# CamBoard.net
KiCad netlist of a schematic drawn in Altium Designer
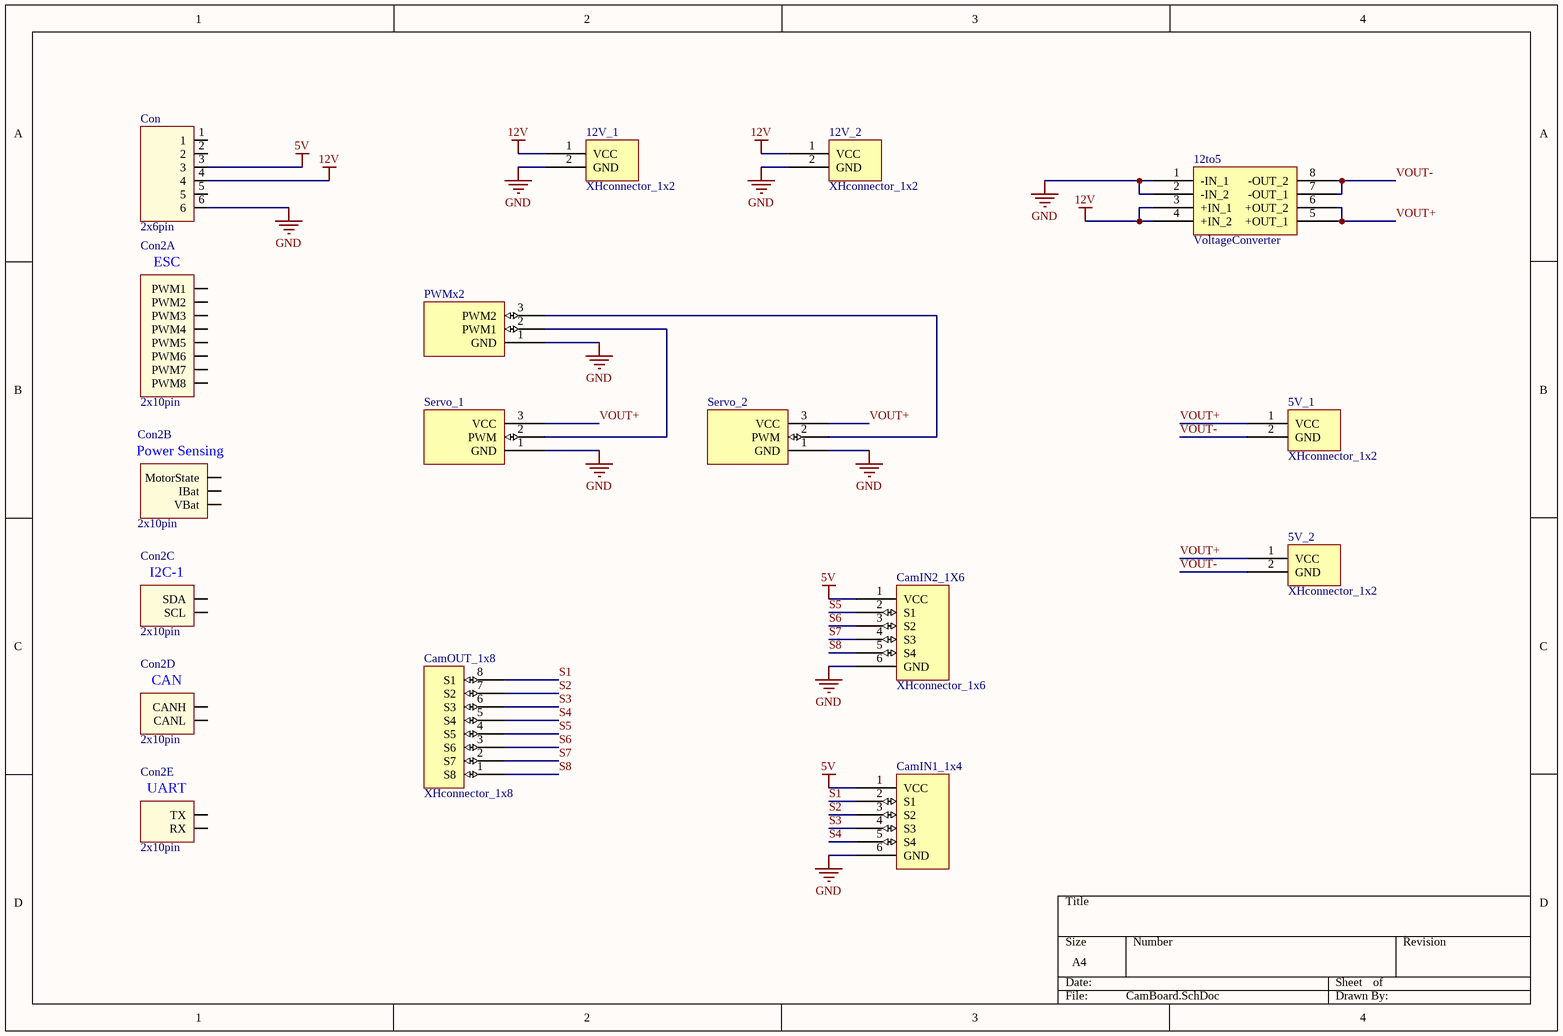
[diagram p0: CamBoard.SchDoc]

(export (version "E")
  (design (tool "Eeschema 10.0.6"))
  (components
    (comp (ref "5V_1")
      (value "XHconnector_1x2")
      (footprint "XH1x2")
      (libsource (lib "Schlib1") (part "XHconnector_1x2"))
    )
    (comp (ref "5V_2")
      (value "XHconnector_1x2")
      (footprint "XH1x2")
      (libsource (lib "Schlib1") (part "XHconnector_1x2"))
    )
    (comp (ref "12to5")
      (value "VoltageConverter")
      (footprint "converter")
      (libsource (lib "Schlib1") (part "VoltageConverter"))
    )
    (comp (ref "12V_1")
      (value "XHconnector_1x2")
      (footprint "XH1x2")
      (libsource (lib "Schlib1") (part "XHconnector_1x2"))
    )
    (comp (ref "12V_2")
      (value "XHconnector_1x2")
      (footprint "XH1x2")
      (libsource (lib "Schlib1") (part "XHconnector_1x2"))
    )
    (comp (ref "CamIN1_1x4")
      (value "XHconnector_1x6")
      (footprint "XH1x6")
      (libsource (lib "Schlib1") (part "XHconnector_1x6"))
    )
    (comp (ref "CamIN2_1X6")
      (value "XHconnector_1x6")
      (footprint "XH1x6")
      (libsource (lib "Schlib1") (part "XHconnector_1x6"))
    )
    (comp (ref "CamOUT_1x8")
      (value "XHconnector_1x8")
      (footprint "XH1x8")
      (libsource (lib "Schlib1") (part "XHconnector_1x8"))
    )
    (comp (ref "Con") (value "2x6pin") (footprint "2x6pin") (libsource (lib "Schlib1") (part "2x6pin")))
    (comp (ref "Con2") (value "2x10pin") (footprint "2x10pin") (libsource (lib "Schlib1") (part "2x10pin")))
    (comp (ref "PWMx2") (value "PWMx2") (footprint "XH1x3") (libsource (lib "Schlib1") (part "PWMx2")))
    (comp (ref "Servo_1") (value "Servo") (footprint "XH1x3") (libsource (lib "Schlib1") (part "Servo")))
    (comp (ref "Servo_2") (value "Servo") (footprint "XH1x3") (libsource (lib "Schlib1") (part "Servo")))
  )
  (nets
    (net (code "1") (name "/S1") (class "Default")
      (node (ref "CamIN1_1x4") (pin "2") (pinfunction "S1_2") (pintype "bidirectional"))
      (node (ref "CamOUT_1x8") (pin "8") (pinfunction "S1_8") (pintype "bidirectional"))
    )
    (net (code "2") (name "/S2") (class "Default")
      (node (ref "CamIN1_1x4") (pin "3") (pinfunction "S2_3") (pintype "bidirectional"))
      (node (ref "CamOUT_1x8") (pin "7") (pinfunction "S2_7") (pintype "bidirectional"))
    )
    (net (code "3") (name "/S3") (class "Default")
      (node (ref "CamIN1_1x4") (pin "4") (pinfunction "S3_4") (pintype "bidirectional"))
      (node (ref "CamOUT_1x8") (pin "6") (pinfunction "S3_6") (pintype "bidirectional"))
    )
    (net (code "4") (name "/S4") (class "Default")
      (node (ref "CamIN1_1x4") (pin "5") (pinfunction "S4_5") (pintype "bidirectional"))
      (node (ref "CamOUT_1x8") (pin "5") (pinfunction "S4_5") (pintype "bidirectional"))
    )
    (net (code "5") (name "/S5") (class "Default")
      (node (ref "CamIN2_1X6") (pin "2") (pinfunction "S1_2") (pintype "bidirectional"))
      (node (ref "CamOUT_1x8") (pin "4") (pinfunction "S5_4") (pintype "bidirectional"))
    )
    (net (code "6") (name "/S6") (class "Default")
      (node (ref "CamIN2_1X6") (pin "3") (pinfunction "S2_3") (pintype "bidirectional"))
      (node (ref "CamOUT_1x8") (pin "3") (pinfunction "S6_3") (pintype "bidirectional"))
    )
    (net (code "7") (name "/S7") (class "Default")
      (node (ref "CamIN2_1X6") (pin "4") (pinfunction "S3_4") (pintype "bidirectional"))
      (node (ref "CamOUT_1x8") (pin "2") (pinfunction "S7_2") (pintype "bidirectional"))
    )
    (net (code "8") (name "/S8") (class "Default")
      (node (ref "CamIN2_1X6") (pin "5") (pinfunction "S4_5") (pintype "bidirectional"))
      (node (ref "CamOUT_1x8") (pin "1") (pinfunction "S8_1") (pintype "bidirectional"))
    )
    (net (code "9") (name "/VOUT+") (class "Default")
      (node (ref "12to5") (pin "5") (pinfunction "+OUT_1_5") (pintype "passive"))
      (node (ref "12to5") (pin "6") (pinfunction "+OUT_2_6") (pintype "passive"))
      (node (ref "5V_1") (pin "1") (pinfunction "VCC_1") (pintype "power_in"))
      (node (ref "5V_2") (pin "1") (pinfunction "VCC_1") (pintype "power_in"))
      (node (ref "Servo_1") (pin "3") (pinfunction "VCC_3") (pintype "power_in"))
      (node (ref "Servo_2") (pin "3") (pinfunction "VCC_3") (pintype "power_in"))
    )
    (net (code "10") (name "/VOUT-") (class "Default")
      (node (ref "12to5") (pin "7") (pinfunction "-OUT_1_7") (pintype "power_in"))
      (node (ref "12to5") (pin "8") (pinfunction "-OUT_2_8") (pintype "power_in"))
      (node (ref "5V_1") (pin "2") (pinfunction "GND_2") (pintype "power_in"))
      (node (ref "5V_2") (pin "2") (pinfunction "GND_2") (pintype "power_in"))
    )
    (net (code "11") (name "5V") (class "Default")
      (node (ref "CamIN1_1x4") (pin "1") (pinfunction "VCC_1") (pintype "power_in"))
      (node (ref "CamIN2_1X6") (pin "1") (pinfunction "VCC_1") (pintype "power_in"))
      (node (ref "Con") (pin "3") (pinfunction "3_3") (pintype "power_in"))
    )
    (net (code "12") (name "12V") (class "Default")
      (node (ref "12V_1") (pin "1") (pinfunction "VCC_1") (pintype "power_in"))
      (node (ref "12V_2") (pin "1") (pinfunction "VCC_1") (pintype "power_in"))
      (node (ref "12to5") (pin "3") (pinfunction "+IN_1_3") (pintype "power_in"))
      (node (ref "12to5") (pin "4") (pinfunction "+IN_2_4") (pintype "power_in"))
      (node (ref "Con") (pin "4") (pinfunction "4_4") (pintype "power_in"))
    )
    (net (code "13") (name "GND") (class "Default")
      (node (ref "12V_1") (pin "2") (pinfunction "GND_2") (pintype "power_in"))
      (node (ref "12V_2") (pin "2") (pinfunction "GND_2") (pintype "power_in"))
      (node (ref "12to5") (pin "1") (pinfunction "-IN_1_1") (pintype "passive"))
      (node (ref "12to5") (pin "2") (pinfunction "-IN_2_2") (pintype "passive"))
      (node (ref "CamIN1_1x4") (pin "6") (pinfunction "GND_6") (pintype "power_in"))
      (node (ref "CamIN2_1X6") (pin "6") (pinfunction "GND_6") (pintype "power_in"))
      (node (ref "Con") (pin "6") (pinfunction "6_6") (pintype "power_in"))
      (node (ref "PWMx2") (pin "1") (pinfunction "GND_1") (pintype "power_in"))
      (node (ref "Servo_1") (pin "1") (pinfunction "GND_1") (pintype "power_in"))
      (node (ref "Servo_2") (pin "1") (pinfunction "GND_1") (pintype "power_in"))
    )
    (net (code "14") (name "Net-(PWMx2-PWM1)") (class "Default")
      (node (ref "PWMx2") (pin "2") (pinfunction "PWM1_2") (pintype "bidirectional"))
      (node (ref "Servo_1") (pin "2") (pinfunction "PWM_2") (pintype "bidirectional"))
    )
    (net (code "15") (name "Net-(PWMx2-PWM2)") (class "Default")
      (node (ref "PWMx2") (pin "3") (pinfunction "PWM2_3") (pintype "bidirectional"))
      (node (ref "Servo_2") (pin "2") (pinfunction "PWM_2") (pintype "bidirectional"))
    )
    (net (code "16") (name "unconnected-(Con-Pad1)") (class "Default")
      (node (ref "Con") (pin "1") (pinfunction "1_1") (pintype "power_in"))
    )
    (net (code "17") (name "unconnected-(Con-Pad2)") (class "Default")
      (node (ref "Con") (pin "2") (pinfunction "2_2") (pintype "power_in"))
    )
    (net (code "18") (name "unconnected-(Con-Pad5)") (class "Default")
      (node (ref "Con") (pin "5") (pinfunction "5_5") (pintype "power_in"))
    )
    (net (code "19") (name "unconnected-(Con2A-PWM1-Pad1)") (class "Default")
      (node (ref "Con2") (pin "1") (pinfunction "PWM1_1") (pintype "passive"))
    )
    (net (code "20") (name "unconnected-(Con2A-PWM2-Pad2)") (class "Default")
      (node (ref "Con2") (pin "2") (pinfunction "PWM2_2") (pintype "passive"))
    )
    (net (code "21") (name "unconnected-(Con2A-PWM3-Pad3)") (class "Default")
      (node (ref "Con2") (pin "3") (pinfunction "PWM3_3") (pintype "passive"))
    )
    (net (code "22") (name "unconnected-(Con2A-PWM4-Pad4)") (class "Default")
      (node (ref "Con2") (pin "4") (pinfunction "PWM4_4") (pintype "passive"))
    )
    (net (code "23") (name "unconnected-(Con2A-PWM5-Pad5)") (class "Default")
      (node (ref "Con2") (pin "5") (pinfunction "PWM5_5") (pintype "passive"))
    )
    (net (code "24") (name "unconnected-(Con2A-PWM6-Pad6)") (class "Default")
      (node (ref "Con2") (pin "6") (pinfunction "PWM6_6") (pintype "passive"))
    )
    (net (code "25") (name "unconnected-(Con2A-PWM7-Pad7)") (class "Default")
      (node (ref "Con2") (pin "7") (pinfunction "PWM7_7") (pintype "passive"))
    )
    (net (code "26") (name "unconnected-(Con2A-PWM8-Pad8)") (class "Default")
      (node (ref "Con2") (pin "8") (pinfunction "PWM8_8") (pintype "passive"))
    )
    (net (code "27") (name "unconnected-(Con2B-IBat-Pad11)") (class "Default")
      (node (ref "Con2") (pin "11") (pinfunction "IBat_11") (pintype "passive"))
    )
    (net (code "28") (name "unconnected-(Con2B-MotorState-Pad10)") (class "Default")
      (node (ref "Con2") (pin "10") (pinfunction "MotorState_10") (pintype "passive"))
    )
    (net (code "29") (name "unconnected-(Con2B-VBat-Pad12)") (class "Default")
      (node (ref "Con2") (pin "12") (pinfunction "VBat_12") (pintype "passive"))
    )
    (net (code "30") (name "unconnected-(Con2C-SCL-Pad14)") (class "Default")
      (node (ref "Con2") (pin "14") (pinfunction "SCL_14") (pintype "passive"))
    )
    (net (code "31") (name "unconnected-(Con2C-SDA-Pad13)") (class "Default")
      (node (ref "Con2") (pin "13") (pinfunction "SDA_13") (pintype "passive"))
    )
    (net (code "32") (name "unconnected-(Con2D-CANH-Pad15)") (class "Default")
      (node (ref "Con2") (pin "15") (pinfunction "CANH_15") (pintype "passive"))
    )
    (net (code "33") (name "unconnected-(Con2D-CANL-Pad16)") (class "Default")
      (node (ref "Con2") (pin "16") (pinfunction "CANL_16") (pintype "passive"))
    )
    (net (code "34") (name "unconnected-(Con2E-RX-Pad20)") (class "Default")
      (node (ref "Con2") (pin "20") (pinfunction "RX_20") (pintype "passive"))
    )
    (net (code "35") (name "unconnected-(Con2E-TX-Pad19)") (class "Default")
      (node (ref "Con2") (pin "19") (pinfunction "TX_19") (pintype "passive"))
    )
  )
)
